# subckt_level_shifter.net
KiCad netlist of a schematic drawn in Altium Designer
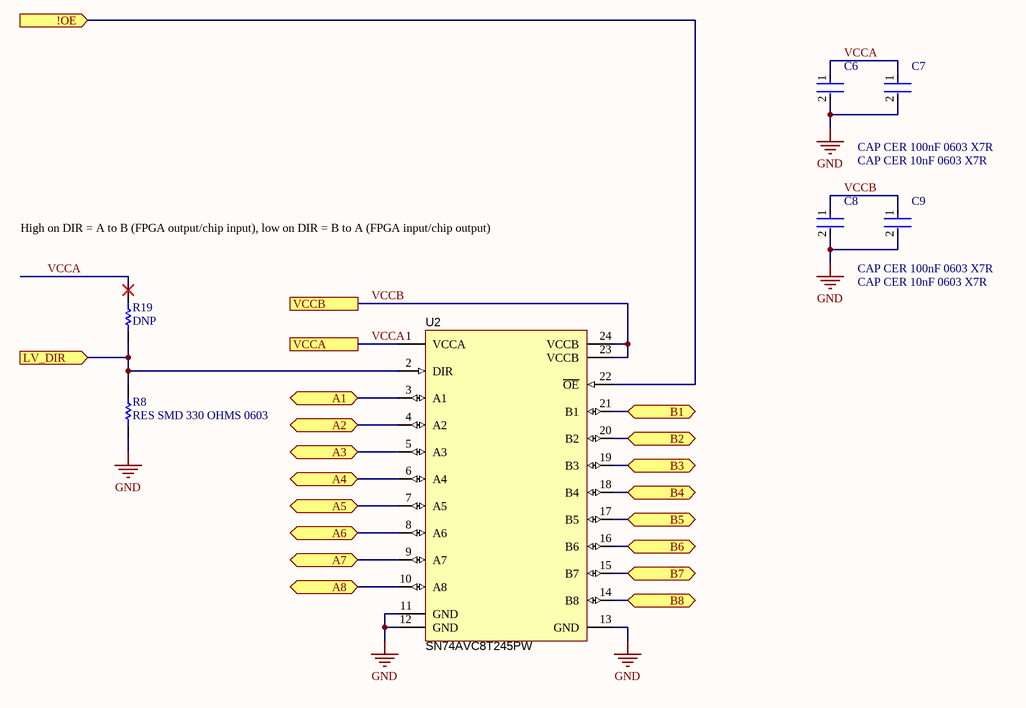
[diagram p0: subckt_level_shifter.SchDoc]

(export (version "E")
  (design (tool "Eeschema 10.0.6"))
  (components
    (comp (ref "C6")
      (value "CAP CER 100nF 0603 X7R")
      (footprint "FP-CC0603-DA-MFG")
      (description "CAP CER 0.1UF 16V X7R 0603")
      (fields
        (field (name "OCTOPART") "https://octopart.com/cc0603krx7r7bb104-yageo-192941")
        (field (name "TOLERANCE") "0.1")
      )
      (libsource (lib "Altium Content Vault") (part "11868f565c42a9108669ba33697ecf6"))
    )
    (comp (ref "C7")
      (value "CAP CER 10nF 0603 X7R")
      (footprint "FP-CC0603-DA-MFG")
      (description "CAP CER 0.1UF 16V X7R 0603")
      (fields
        (field (name "OCTOPART") "https://octopart.com/cc0603krx7r7bb104-yageo-192941")
        (field (name "TOLERANCE") "0.1")
      )
      (libsource (lib "Altium Content Vault") (part "11868f565c42a9108669ba33697ecf6"))
    )
    (comp (ref "C8")
      (value "CAP CER 100nF 0603 X7R")
      (footprint "FP-CC0603-DA-MFG")
      (description "CAP CER 0.1UF 16V X7R 0603")
      (fields
        (field (name "OCTOPART") "https://octopart.com/cc0603krx7r7bb104-yageo-192941")
        (field (name "TOLERANCE") "0.1")
      )
      (libsource (lib "Altium Content Vault") (part "11868f565c42a9108669ba33697ecf6"))
    )
    (comp (ref "C9")
      (value "CAP CER 10nF 0603 X7R")
      (footprint "FP-CC0603-DA-MFG")
      (description "CAP CER 0.1UF 16V X7R 0603")
      (fields
        (field (name "OCTOPART") "https://octopart.com/cc0603krx7r7bb104-yageo-192941")
        (field (name "TOLERANCE") "0.1")
      )
      (libsource (lib "Altium Content Vault") (part "11868f565c42a9108669ba33697ecf6"))
    )
    (comp (ref "R8")
      (value "RES SMD 330 OHMS 0603")
      (footprint "RESC1609X50X30LL10T20")
      (description "DNP")
      (fields (field (name "PART NUMBER") "CRCW0603100KFKEA") (field (name "MANUFACTURER") "Vishay Dale"))
      (libsource (lib "Altium Content Vault") (part "RES"))
    )
    (comp (ref "R19")
      (value "DNP")
      (footprint "RESC1609X50X30LL10T20")
      (fields (field (name "PART NUMBER") "CRCW0603100KFKEA") (field (name "MANUFACTURER") "Vishay Dale"))
      (libsource (lib "Altium Content Vault") (part "RES"))
    )
    (comp (ref "U2")
      (value "SN74AVC8T245PW")
      (footprint "PW0024A_N")
      (fields
        (field (name "MANUFACTURER") "Texas Instruments")
        (field (name "SYMBOLCREATOR") "a0411947")
        (field (name "PUBLISHER") "Texas Instruments")
      )
      (libsource (lib "TIDA-00172_revE2") (part "SN74AVC8T245PW"))
    )
  )
  (nets
    (net (code "1") (name "/!OE") (class "Default")
      (node (ref "U2") (pin "22") (pinfunction "OE_22") (pintype "input"))
    )
    (net (code "2") (name "/A1") (class "Default")
      (node (ref "U2") (pin "3") (pinfunction "A1_3") (pintype "bidirectional"))
    )
    (net (code "3") (name "/A2") (class "Default")
      (node (ref "U2") (pin "4") (pinfunction "A2_4") (pintype "bidirectional"))
    )
    (net (code "4") (name "/A3") (class "Default")
      (node (ref "U2") (pin "5") (pinfunction "A3_5") (pintype "bidirectional"))
    )
    (net (code "5") (name "/A4") (class "Default")
      (node (ref "U2") (pin "6") (pinfunction "A4_6") (pintype "bidirectional"))
    )
    (net (code "6") (name "/A5") (class "Default")
      (node (ref "U2") (pin "7") (pinfunction "A5_7") (pintype "bidirectional"))
    )
    (net (code "7") (name "/A6") (class "Default")
      (node (ref "U2") (pin "8") (pinfunction "A6_8") (pintype "bidirectional"))
    )
    (net (code "8") (name "/A7") (class "Default")
      (node (ref "U2") (pin "9") (pinfunction "A7_9") (pintype "bidirectional"))
    )
    (net (code "9") (name "/A8") (class "Default")
      (node (ref "U2") (pin "10") (pinfunction "A8_10") (pintype "bidirectional"))
    )
    (net (code "10") (name "/B1") (class "Default")
      (node (ref "U2") (pin "21") (pinfunction "B1_21") (pintype "bidirectional"))
    )
    (net (code "11") (name "/B2") (class "Default")
      (node (ref "U2") (pin "20") (pinfunction "B2_20") (pintype "bidirectional"))
    )
    (net (code "12") (name "/B3") (class "Default")
      (node (ref "U2") (pin "19") (pinfunction "B3_19") (pintype "bidirectional"))
    )
    (net (code "13") (name "/B4") (class "Default")
      (node (ref "U2") (pin "18") (pinfunction "B4_18") (pintype "bidirectional"))
    )
    (net (code "14") (name "/B5") (class "Default")
      (node (ref "U2") (pin "17") (pinfunction "B5_17") (pintype "bidirectional"))
    )
    (net (code "15") (name "/B6") (class "Default")
      (node (ref "U2") (pin "16") (pinfunction "B6_16") (pintype "bidirectional"))
    )
    (net (code "16") (name "/B7") (class "Default")
      (node (ref "U2") (pin "15") (pinfunction "B7_15") (pintype "bidirectional"))
    )
    (net (code "17") (name "/B8") (class "Default")
      (node (ref "U2") (pin "14") (pinfunction "B8_14") (pintype "bidirectional"))
    )
    (net (code "18") (name "/LV_DIR") (class "Default")
      (node (ref "R19") (pin "2") (pinfunction "2_2") (pintype "passive"))
      (node (ref "R8") (pin "1") (pinfunction "1_1") (pintype "passive"))
      (node (ref "U2") (pin "2") (pinfunction "DIR_2") (pintype "input"))
    )
    (net (code "19") (name "/VCCA") (class "Default")
      (node (ref "C6") (pin "1") (pinfunction "1_1") (pintype "passive"))
      (node (ref "C7") (pin "1") (pinfunction "1_1") (pintype "passive"))
      (node (ref "R19") (pin "1") (pinfunction "1_1") (pintype "passive"))
      (node (ref "U2") (pin "1") (pinfunction "VCCA_1") (pintype "power_in"))
    )
    (net (code "20") (name "/VCCB") (class "Default")
      (node (ref "C8") (pin "1") (pinfunction "1_1") (pintype "passive"))
      (node (ref "C9") (pin "1") (pinfunction "1_1") (pintype "passive"))
      (node (ref "U2") (pin "23") (pinfunction "VCCB_23") (pintype "power_in"))
      (node (ref "U2") (pin "24") (pinfunction "VCCB_24") (pintype "power_in"))
    )
    (net (code "21") (name "GND") (class "Default")
      (node (ref "C6") (pin "2") (pinfunction "2_2") (pintype "passive"))
      (node (ref "C7") (pin "2") (pinfunction "2_2") (pintype "passive"))
      (node (ref "C8") (pin "2") (pinfunction "2_2") (pintype "passive"))
      (node (ref "C9") (pin "2") (pinfunction "2_2") (pintype "passive"))
      (node (ref "R8") (pin "2") (pinfunction "2_2") (pintype "passive"))
      (node (ref "U2") (pin "11") (pinfunction "GND_11") (pintype "power_in"))
      (node (ref "U2") (pin "12") (pinfunction "GND_12") (pintype "power_in"))
      (node (ref "U2") (pin "13") (pinfunction "GND_13") (pintype "power_in"))
    )
  )
)
